# Microcontroller.net
KiCad netlist of a schematic drawn in Altium Designer
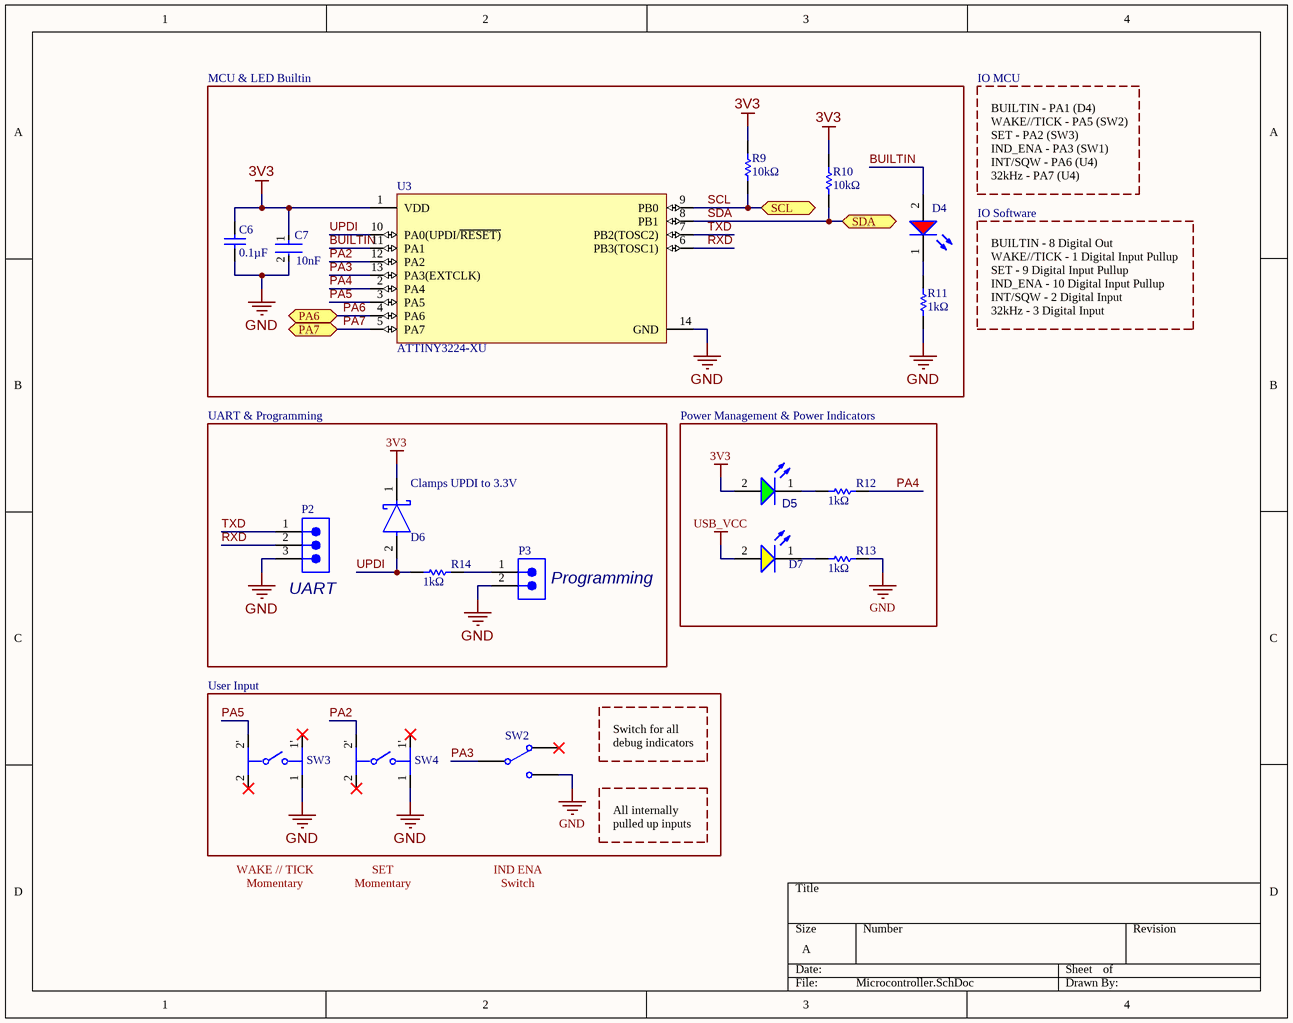
[diagram p0: Microcontroller.SchDoc]

(export (version "E")
  (design (tool "Eeschema 10.0.6"))
  (components
    (comp (ref "C6")
      (value "0.1µF")
      (footprint "CAPC3216X100X50LL20T25")
      (description "Chip Capacitor, 100 nF, +/- 10%, 25 V, -55 to 125 degC, 1206 (3216 Metric), RoHS, Tape and Reel")
      (fields (field (name "MANUFACTURER") "Kemet"))
      (libsource (lib "Altium Content Vault") (part "CAP-NP-2"))
    )
    (comp (ref "C7")
      (value "10nF")
      (footprint "FP-C1206C-EB-MFG")
      (description "CAP CER 10000PF 100V X7R 1206")
      (fields
        (field (name "OCTOPART") "https://octopart.com/c1206c103j1ractu-kemet-121270")
        (field (name "MANUFACTURER") "KEMET")
      )
      (libsource (lib "Altium Content Vault") (part "b4654b650e69147ec39a6b967a45e02"))
    )
    (comp (ref "D4")
      (value "150120RS75000")
      (footprint "WL-SMCW_1206_150120xx75000")
      (description "WL-SMCW SMT Mono-Color Chip LED Waterclear")
      (libsource (lib "Altium Content Vault") (part "LED_Red_2A-1K"))
    )
    (comp (ref "D5")
      (value "150120GS75000")
      (footprint "WL-SMCW_1206_150120xx75000")
      (description "WL-SMCW SMT Mono-Color Chip LED Waterclear")
      (libsource (lib "Altium Content Vault") (part "LED_Green_2A-1K"))
    )
    (comp (ref "D6")
      (value "SS14-E3/61T")
      (footprint "FP-95400-MFG")
      (description "DIODE SCHOTTKY 40V 1A DO214AC")
      (fields
        (field (name "OCTOPART") "https://octopart.com/ss14-e3%2F61t-vishay-39552847")
        (field (name "MANUFACTURER") "Vishay")
      )
      (libsource (lib "Altium Content Vault") (part "1d6ec82d83fb6aee721767c19dac4b9"))
    )
    (comp (ref "D7")
      (value "150120YS75000")
      (footprint "WL-SMCW_1206_150120xx75000")
      (description "Led, Yellow, 590 Nm, 2 V, 30 Ma, 120 Mcd Rohs Compliant: Yes")
      (libsource (lib "Altium Content Vault") (part "LED_Yellow_2A-1K"))
    )
    (comp (ref "P2")
      (value "61300311121")
      (footprint "61300311121")
      (libsource (lib "Altium Content Vault") (part "Header_Male_1R_03P"))
    )
    (comp (ref "P3")
      (value "61300211121")
      (footprint "61300211121")
      (libsource (lib "Altium Content Vault") (part "Header_Male_1R_02P"))
    )
    (comp (ref "R9")
      (value "10kΩ")
      (footprint "RESC3116X65X40LL10T20")
      (description "Chip Resistor, 10 KOhm, +/- 1%, 0.25 W, -55 to 155 degC, 1206 (3216 Metric), RoHS, Tape and Reel")
      (fields (field (name "TOLERANCE") "1%") (field (name "MANUFACTURER") "Yageo"))
      (libsource (lib "Altium Content Vault") (part "RES-2"))
    )
    (comp (ref "R10")
      (value "10kΩ")
      (footprint "RESC3116X65X40LL10T20")
      (description "Chip Resistor, 10 KOhm, +/- 1%, 0.25 W, -55 to 155 degC, 1206 (3216 Metric), RoHS, Tape and Reel")
      (fields (field (name "TOLERANCE") "1%") (field (name "MANUFACTURER") "Yageo"))
      (libsource (lib "Altium Content Vault") (part "RES-2"))
    )
    (comp (ref "R11")
      (value "1kΩ")
      (footprint "RESC3116X65X40LL10T20")
      (description "Chip Resistor, 1 KOhm, +/- 1%, 0.25 W, -55 to 155 degC, 1206 (3216 Metric), RoHS, Tape and Reel")
      (fields (field (name "TOLERANCE") "1%") (field (name "MANUFACTURER") "Yageo"))
      (libsource (lib "Altium Content Vault") (part "RES-2"))
    )
    (comp (ref "R12")
      (value "1kΩ")
      (footprint "RESC3116X65X40LL10T20")
      (description "Chip Resistor, 1 KOhm, +/- 1%, 0.25 W, -55 to 155 degC, 1206 (3216 Metric), RoHS, Tape and Reel")
      (fields (field (name "TOLERANCE") "1%") (field (name "MANUFACTURER") "Yageo"))
      (libsource (lib "Altium Content Vault") (part "RES-2"))
    )
    (comp (ref "R13")
      (value "1kΩ")
      (footprint "RESC3116X65X40LL10T20")
      (description "Chip Resistor, 1 KOhm, +/- 1%, 0.25 W, -55 to 155 degC, 1206 (3216 Metric), RoHS, Tape and Reel")
      (fields (field (name "TOLERANCE") "1%") (field (name "MANUFACTURER") "Yageo"))
      (libsource (lib "Altium Content Vault") (part "RES-2"))
    )
    (comp (ref "R14")
      (value "1kΩ")
      (footprint "RESC3116X65X40LL10T20")
      (description "Chip Resistor, 1 KOhm, +/- 1%, 0.25 W, -55 to 155 degC, 1206 (3216 Metric), RoHS, Tape and Reel")
      (fields (field (name "TOLERANCE") "1%") (field (name "MANUFACTURER") "Yageo"))
      (libsource (lib "Altium Content Vault") (part "RES-2"))
    )
    (comp (ref "SW2")
      (value "450404015514")
      (footprint "450404015514")
      (description "450404015514 Slide Switch, 0.3A, 5Vdc, Smd Rohs Compliant: Yes")
      (libsource (lib "Altium Content Vault") (part "SPDT"))
    )
    (comp (ref "SW3")
      (value "EVQ-9P701P")
      (footprint "FP-EVQ-9P701P-MFG")
      (description "SWITCH TACTILE SPST-NO 0.05A 12V")
      (fields
        (field (name "MANUFACTURER") "Panasonic")
        (field (name "OCTOPART") "https://octopart.com/evq-9p701p-panasonic-58006746")
      )
      (libsource (lib "Altium Content Vault") (part "67890d47754ac483cb1d3ba3be74b6c"))
    )
    (comp (ref "SW4")
      (value "EVQ-9P701P")
      (footprint "FP-EVQ-9P701P-MFG")
      (description "SWITCH TACTILE SPST-NO 0.05A 12V")
      (fields
        (field (name "MANUFACTURER") "Panasonic")
        (field (name "OCTOPART") "https://octopart.com/evq-9p701p-panasonic-58006746")
      )
      (libsource (lib "Altium Content Vault") (part "67890d47754ac483cb1d3ba3be74b6c"))
    )
    (comp (ref "U3")
      (value "ATTINY3224-XU")
      (footprint "FP-C04-087-ST-MFG")
      (description "ATTINY3224-XU Microcontroller 8-Bit AVR RISC 32KB Flash 1.8V to 5.5V 14-Pin TSSOP Tube")
      (libsource (lib "Altium Content Vault") (part "af96ba96504569538fca35b5c374a83"))
    )
  )
  (nets
    (net (code "1") (name "/BUILTIN") (class "Default")
      (node (ref "D4") (pin "2") (pinfunction "A_2") (pintype "passive"))
      (node (ref "U3") (pin "11") (pinfunction "PA1_11") (pintype "bidirectional"))
    )
    (net (code "2") (name "/PA2") (class "Default")
      (node (ref "SW4") (pin "2'") (pinfunction "2'_2'") (pintype "passive"))
      (node (ref "U3") (pin "12") (pinfunction "PA2_12") (pintype "bidirectional"))
    )
    (net (code "3") (name "/PA3") (class "Default")
      (node (ref "SW2") (pin "COM") (pinfunction "COM_COM") (pintype "passive"))
      (node (ref "U3") (pin "13") (pinfunction "PA3(EXTCLK)_13") (pintype "bidirectional"))
    )
    (net (code "4") (name "/PA4") (class "Default")
      (node (ref "R12") (pin "2") (pinfunction "2_2") (pintype "passive"))
      (node (ref "U3") (pin "2") (pinfunction "PA4_2") (pintype "bidirectional"))
    )
    (net (code "5") (name "/PA5") (class "Default")
      (node (ref "SW3") (pin "2'") (pinfunction "2'_2'") (pintype "passive"))
      (node (ref "U3") (pin "3") (pinfunction "PA5_3") (pintype "bidirectional"))
    )
    (net (code "6") (name "/PA6") (class "Default")
      (node (ref "U3") (pin "4") (pinfunction "PA6_4") (pintype "bidirectional"))
    )
    (net (code "7") (name "/PA7") (class "Default")
      (node (ref "U3") (pin "5") (pinfunction "PA7_5") (pintype "bidirectional"))
    )
    (net (code "8") (name "/RXD") (class "Default")
      (node (ref "P2") (pin "2") (pinfunction "2_2") (pintype "passive"))
      (node (ref "U3") (pin "6") (pinfunction "PB3(TOSC1)_6") (pintype "bidirectional"))
    )
    (net (code "9") (name "/SCL") (class "Default")
      (node (ref "R9") (pin "1") (pinfunction "1_1") (pintype "passive"))
      (node (ref "U3") (pin "9") (pinfunction "PB0_9") (pintype "bidirectional"))
    )
    (net (code "10") (name "/SDA") (class "Default")
      (node (ref "R10") (pin "1") (pinfunction "1_1") (pintype "passive"))
      (node (ref "U3") (pin "8") (pinfunction "PB1_8") (pintype "bidirectional"))
    )
    (net (code "11") (name "/TXD") (class "Default")
      (node (ref "P2") (pin "1") (pinfunction "1_1") (pintype "passive"))
      (node (ref "U3") (pin "7") (pinfunction "PB2(TOSC2)_7") (pintype "bidirectional"))
    )
    (net (code "12") (name "/UPDI") (class "Default")
      (node (ref "D6") (pin "2") (pinfunction "A_2") (pintype "passive"))
      (node (ref "R14") (pin "1") (pinfunction "1_1") (pintype "passive"))
      (node (ref "U3") (pin "10") (pinfunction "PA0(UPDI/~{RESET)}_10") (pintype "bidirectional"))
    )
    (net (code "13") (name "3V3") (class "Default")
      (node (ref "C6") (pin "2") (pinfunction "2_2") (pintype "passive"))
      (node (ref "C7") (pin "1") (pinfunction "1_1") (pintype "passive"))
      (node (ref "D5") (pin "2") (pinfunction "A_2") (pintype "passive"))
      (node (ref "D6") (pin "1") (pinfunction "C_1") (pintype "passive"))
      (node (ref "R10") (pin "2") (pinfunction "2_2") (pintype "passive"))
      (node (ref "R9") (pin "2") (pinfunction "2_2") (pintype "passive"))
      (node (ref "U3") (pin "1") (pinfunction "VDD_1") (pintype "power_in"))
    )
    (net (code "14") (name "GND") (class "Default")
      (node (ref "C6") (pin "1") (pinfunction "1_1") (pintype "passive"))
      (node (ref "C7") (pin "2") (pinfunction "2_2") (pintype "passive"))
      (node (ref "P2") (pin "3") (pinfunction "3_3") (pintype "passive"))
      (node (ref "P3") (pin "2") (pinfunction "2_2") (pintype "passive"))
      (node (ref "R11") (pin "1") (pinfunction "1_1") (pintype "passive"))
      (node (ref "R13") (pin "2") (pinfunction "2_2") (pintype "passive"))
      (node (ref "SW2") (pin "L2") (pinfunction "L2_L2") (pintype "passive"))
      (node (ref "SW3") (pin "1") (pinfunction "1_1") (pintype "passive"))
      (node (ref "SW4") (pin "1") (pinfunction "1_1") (pintype "passive"))
      (node (ref "U3") (pin "14") (pinfunction "GND_14") (pintype "power_in"))
    )
    (net (code "15") (name "Net-(D4-K)") (class "Default")
      (node (ref "D4") (pin "1") (pinfunction "K_1") (pintype "passive"))
      (node (ref "R11") (pin "2") (pinfunction "2_2") (pintype "passive"))
    )
    (net (code "16") (name "Net-(D5-K)") (class "Default")
      (node (ref "D5") (pin "1") (pinfunction "K_1") (pintype "passive"))
      (node (ref "R12") (pin "1") (pinfunction "1_1") (pintype "passive"))
    )
    (net (code "17") (name "Net-(D7-K)") (class "Default")
      (node (ref "D7") (pin "1") (pinfunction "K_1") (pintype "passive"))
      (node (ref "R13") (pin "1") (pinfunction "1_1") (pintype "passive"))
    )
    (net (code "18") (name "Net-(P3-Pad1)") (class "Default")
      (node (ref "P3") (pin "1") (pinfunction "1_1") (pintype "passive"))
      (node (ref "R14") (pin "2") (pinfunction "2_2") (pintype "passive"))
    )
    (net (code "19") (name "USB_VCC") (class "Default")
      (node (ref "D7") (pin "2") (pinfunction "A_2") (pintype "passive"))
    )
    (net (code "20") (name "unconnected-(SW2-PadL1)") (class "Default")
      (node (ref "SW2") (pin "L1") (pinfunction "L1_L1") (pintype "passive+no_connect"))
    )
    (net (code "21") (name "unconnected-(SW3-Pad1')") (class "Default")
      (node (ref "SW3") (pin "1'") (pinfunction "1'_1'") (pintype "passive+no_connect"))
    )
    (net (code "22") (name "unconnected-(SW3-Pad2)") (class "Default")
      (node (ref "SW3") (pin "2") (pinfunction "2_2") (pintype "passive+no_connect"))
    )
    (net (code "23") (name "unconnected-(SW4-Pad1')") (class "Default")
      (node (ref "SW4") (pin "1'") (pinfunction "1'_1'") (pintype "passive+no_connect"))
    )
    (net (code "24") (name "unconnected-(SW4-Pad2)") (class "Default")
      (node (ref "SW4") (pin "2") (pinfunction "2_2") (pintype "passive+no_connect"))
    )
  )
)
